# RP2350.net
KiCad netlist of a schematic drawn in Altium Designer
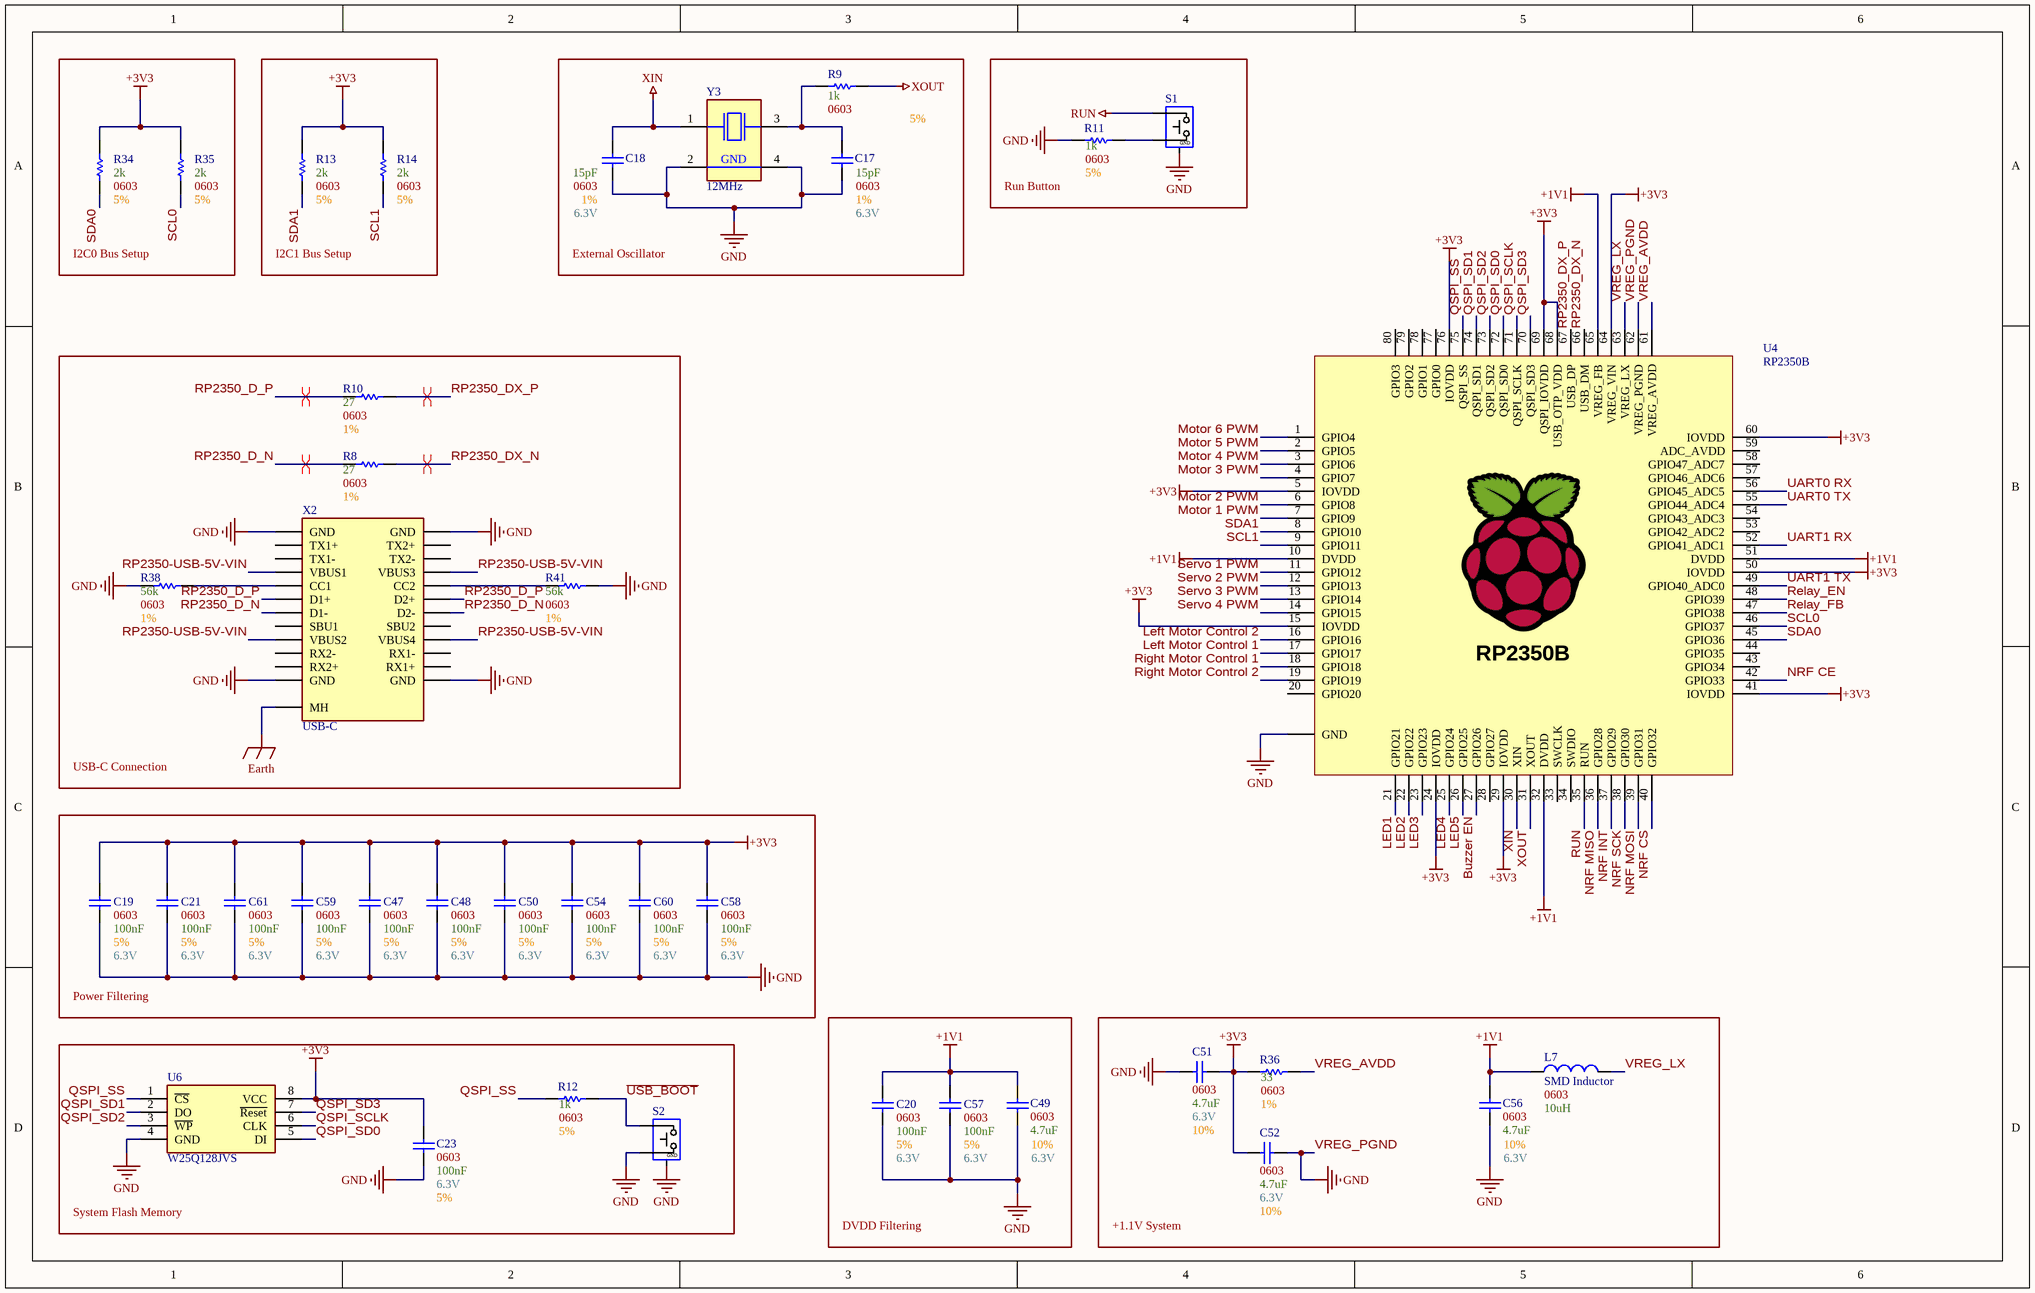
[diagram p0: RP2350.SchDoc]

(export (version "E")
  (design (tool "Eeschema 10.0.6"))
  (components
    (comp (ref "C17")
      (value "[Cap] SMD Nonpolarized")
      (footprint "[Cap] SMD 0603")
      (fields
        (field (name "SIZE PACKAGE") "0603")
        (field (name "CAPACITANCE") "15pF")
        (field (name "VOLTAGE") "6.3V")
        (field (name "TOLERANCE") "1%")
      )
      (libsource (lib "RADM Components") (part "[Cap] SMD Nonpolarized"))
    )
    (comp (ref "C18")
      (value "[Cap] SMD Nonpolarized")
      (footprint "[Cap] SMD 0603")
      (fields
        (field (name "SIZE PACKAGE") "0603")
        (field (name "CAPACITANCE") "15pF")
        (field (name "VOLTAGE") "6.3V")
        (field (name "TOLERANCE") "1%")
      )
      (libsource (lib "RADM Components") (part "[Cap] SMD Nonpolarized"))
    )
    (comp (ref "C19")
      (value "[Cap] SMD Nonpolarized")
      (footprint "[Cap] SMD 0603")
      (fields
        (field (name "SIZE PACKAGE") "0603")
        (field (name "CAPACITANCE") "100nF")
        (field (name "VOLTAGE") "6.3V")
        (field (name "TOLERANCE") "5%")
      )
      (libsource (lib "RADM Components") (part "[Cap] SMD Nonpolarized"))
    )
    (comp (ref "C20")
      (value "[Cap] SMD Nonpolarized")
      (footprint "[Cap] SMD 0603")
      (fields
        (field (name "SIZE PACKAGE") "0603")
        (field (name "CAPACITANCE") "100nF")
        (field (name "VOLTAGE") "6.3V")
        (field (name "TOLERANCE") "5%")
      )
      (libsource (lib "RADM Components") (part "[Cap] SMD Nonpolarized"))
    )
    (comp (ref "C21")
      (value "[Cap] SMD Nonpolarized")
      (footprint "[Cap] SMD 0603")
      (fields
        (field (name "SIZE PACKAGE") "0603")
        (field (name "CAPACITANCE") "100nF")
        (field (name "VOLTAGE") "6.3V")
        (field (name "TOLERANCE") "5%")
      )
      (libsource (lib "RADM Components") (part "[Cap] SMD Nonpolarized"))
    )
    (comp (ref "C23")
      (value "[Cap] SMD Nonpolarized")
      (footprint "[Cap] SMD 0603")
      (fields
        (field (name "SIZE PACKAGE") "0603")
        (field (name "CAPACITANCE") "100nF")
        (field (name "VOLTAGE") "6.3V")
        (field (name "TOLERANCE") "5%")
      )
      (libsource (lib "RADM Components") (part "[Cap] SMD Nonpolarized"))
    )
    (comp (ref "C47")
      (value "[Cap] SMD Nonpolarized")
      (footprint "[Cap] SMD 0603")
      (fields
        (field (name "SIZE PACKAGE") "0603")
        (field (name "CAPACITANCE") "100nF")
        (field (name "VOLTAGE") "6.3V")
        (field (name "TOLERANCE") "5%")
      )
      (libsource (lib "RADM Components") (part "[Cap] SMD Nonpolarized"))
    )
    (comp (ref "C48")
      (value "[Cap] SMD Nonpolarized")
      (footprint "[Cap] SMD 0603")
      (fields
        (field (name "SIZE PACKAGE") "0603")
        (field (name "CAPACITANCE") "100nF")
        (field (name "VOLTAGE") "6.3V")
        (field (name "TOLERANCE") "5%")
      )
      (libsource (lib "RADM Components") (part "[Cap] SMD Nonpolarized"))
    )
    (comp (ref "C49")
      (value "[Cap] SMD Nonpolarized")
      (footprint "[Cap] SMD 0603")
      (fields
        (field (name "SIZE PACKAGE") "0603")
        (field (name "CAPACITANCE") "4.7uF")
        (field (name "VOLTAGE") "6.3V")
        (field (name "TOLERANCE") "10%")
      )
      (libsource (lib "RADM Components") (part "[Cap] SMD Nonpolarized"))
    )
    (comp (ref "C50")
      (value "[Cap] SMD Nonpolarized")
      (footprint "[Cap] SMD 0603")
      (fields
        (field (name "SIZE PACKAGE") "0603")
        (field (name "CAPACITANCE") "100nF")
        (field (name "VOLTAGE") "6.3V")
        (field (name "TOLERANCE") "5%")
      )
      (libsource (lib "RADM Components") (part "[Cap] SMD Nonpolarized"))
    )
    (comp (ref "C51")
      (value "[Cap] SMD Nonpolarized")
      (footprint "[Cap] SMD 0603")
      (fields
        (field (name "SIZE PACKAGE") "0603")
        (field (name "CAPACITANCE") "4.7uF")
        (field (name "VOLTAGE") "6.3V")
        (field (name "TOLERANCE") "10%")
      )
      (libsource (lib "RADM Components") (part "[Cap] SMD Nonpolarized"))
    )
    (comp (ref "C52")
      (value "[Cap] SMD Nonpolarized")
      (footprint "[Cap] SMD 0603")
      (fields
        (field (name "SIZE PACKAGE") "0603")
        (field (name "CAPACITANCE") "4.7uF")
        (field (name "VOLTAGE") "6.3V")
        (field (name "TOLERANCE") "10%")
      )
      (libsource (lib "RADM Components") (part "[Cap] SMD Nonpolarized"))
    )
    (comp (ref "C54")
      (value "[Cap] SMD Nonpolarized")
      (footprint "[Cap] SMD 0603")
      (fields
        (field (name "SIZE PACKAGE") "0603")
        (field (name "CAPACITANCE") "100nF")
        (field (name "VOLTAGE") "6.3V")
        (field (name "TOLERANCE") "5%")
      )
      (libsource (lib "RADM Components") (part "[Cap] SMD Nonpolarized"))
    )
    (comp (ref "C56")
      (value "[Cap] SMD Nonpolarized")
      (footprint "[Cap] SMD 0603")
      (fields
        (field (name "SIZE PACKAGE") "0603")
        (field (name "CAPACITANCE") "4.7uF")
        (field (name "VOLTAGE") "6.3V")
        (field (name "TOLERANCE") "10%")
      )
      (libsource (lib "RADM Components") (part "[Cap] SMD Nonpolarized"))
    )
    (comp (ref "C57")
      (value "[Cap] SMD Nonpolarized")
      (footprint "[Cap] SMD 0603")
      (fields
        (field (name "SIZE PACKAGE") "0603")
        (field (name "CAPACITANCE") "100nF")
        (field (name "VOLTAGE") "6.3V")
        (field (name "TOLERANCE") "5%")
      )
      (libsource (lib "RADM Components") (part "[Cap] SMD Nonpolarized"))
    )
    (comp (ref "C58")
      (value "[Cap] SMD Nonpolarized")
      (footprint "[Cap] SMD 0603")
      (fields
        (field (name "SIZE PACKAGE") "0603")
        (field (name "CAPACITANCE") "100nF")
        (field (name "VOLTAGE") "6.3V")
        (field (name "TOLERANCE") "5%")
      )
      (libsource (lib "RADM Components") (part "[Cap] SMD Nonpolarized"))
    )
    (comp (ref "C59")
      (value "[Cap] SMD Nonpolarized")
      (footprint "[Cap] SMD 0603")
      (fields
        (field (name "SIZE PACKAGE") "0603")
        (field (name "CAPACITANCE") "100nF")
        (field (name "VOLTAGE") "6.3V")
        (field (name "TOLERANCE") "5%")
      )
      (libsource (lib "RADM Components") (part "[Cap] SMD Nonpolarized"))
    )
    (comp (ref "C60")
      (value "[Cap] SMD Nonpolarized")
      (footprint "[Cap] SMD 0603")
      (fields
        (field (name "SIZE PACKAGE") "0603")
        (field (name "CAPACITANCE") "100nF")
        (field (name "VOLTAGE") "6.3V")
        (field (name "TOLERANCE") "5%")
      )
      (libsource (lib "RADM Components") (part "[Cap] SMD Nonpolarized"))
    )
    (comp (ref "C61")
      (value "[Cap] SMD Nonpolarized")
      (footprint "[Cap] SMD 0603")
      (fields
        (field (name "SIZE PACKAGE") "0603")
        (field (name "CAPACITANCE") "100nF")
        (field (name "VOLTAGE") "6.3V")
        (field (name "TOLERANCE") "5%")
      )
      (libsource (lib "RADM Components") (part "[Cap] SMD Nonpolarized"))
    )
    (comp (ref "L7")
      (value "SMD Inductor")
      (footprint "[Inductor] SMD 0603")
      (fields (field (name "SIZE PACKAGE") "0603") (field (name "INDUCTANCE") "10uH"))
      (libsource (lib "RADM Components") (part "[Inductor] SMD Inductor"))
    )
    (comp (ref "R8")
      (value "[Res] SMD Resistor")
      (footprint "[Res] SMD 0603")
      (description "Generic")
      (fields
        (field (name "TOLERANCE") "1%")
        (field (name "RESISTANCE") "27")
        (field (name "SIZE PACKAGE") "0603")
      )
      (libsource (lib "RADM Components") (part "[Res] SMD Resistor"))
    )
    (comp (ref "R9")
      (value "[Res] SMD Resistor")
      (footprint "[Res] SMD 0603")
      (description "Generic")
      (fields
        (field (name "RESISTANCE") "1k")
        (field (name "SIZE PACKAGE") "0603")
        (field (name "TOLERANCE") "5%")
      )
      (libsource (lib "RADM Components") (part "[Res] SMD Resistor"))
    )
    (comp (ref "R10")
      (value "[Res] SMD Resistor")
      (footprint "[Res] SMD 0603")
      (description "Generic")
      (fields
        (field (name "TOLERANCE") "1%")
        (field (name "RESISTANCE") "27")
        (field (name "SIZE PACKAGE") "0603")
      )
      (libsource (lib "RADM Components") (part "[Res] SMD Resistor"))
    )
    (comp (ref "R11")
      (value "[Res] SMD Resistor")
      (footprint "[Res] SMD 0603")
      (description "Generic")
      (fields
        (field (name "RESISTANCE") "1k")
        (field (name "SIZE PACKAGE") "0603")
        (field (name "TOLERANCE") "5%")
      )
      (libsource (lib "RADM Components") (part "[Res] SMD Resistor"))
    )
    (comp (ref "R12")
      (value "[Res] SMD Resistor")
      (footprint "[Res] SMD 0603")
      (description "Generic")
      (fields
        (field (name "RESISTANCE") "1k")
        (field (name "SIZE PACKAGE") "0603")
        (field (name "TOLERANCE") "5%")
      )
      (libsource (lib "RADM Components") (part "[Res] SMD Resistor"))
    )
    (comp (ref "R13")
      (value "[Res] SMD Resistor")
      (footprint "[Res] SMD 0603")
      (description "Generic")
      (fields
        (field (name "RESISTANCE") "2k")
        (field (name "SIZE PACKAGE") "0603")
        (field (name "TOLERANCE") "5%")
      )
      (libsource (lib "RADM Components") (part "[Res] SMD Resistor"))
    )
    (comp (ref "R14")
      (value "[Res] SMD Resistor")
      (footprint "[Res] SMD 0603")
      (description "Generic")
      (fields
        (field (name "RESISTANCE") "2k")
        (field (name "SIZE PACKAGE") "0603")
        (field (name "TOLERANCE") "5%")
      )
      (libsource (lib "RADM Components") (part "[Res] SMD Resistor"))
    )
    (comp (ref "R34")
      (value "[Res] SMD Resistor")
      (footprint "[Res] SMD 0603")
      (description "Generic")
      (fields
        (field (name "RESISTANCE") "2k")
        (field (name "SIZE PACKAGE") "0603")
        (field (name "TOLERANCE") "5%")
      )
      (libsource (lib "RADM Components") (part "[Res] SMD Resistor"))
    )
    (comp (ref "R35")
      (value "[Res] SMD Resistor")
      (footprint "[Res] SMD 0603")
      (description "Generic")
      (fields
        (field (name "RESISTANCE") "2k")
        (field (name "SIZE PACKAGE") "0603")
        (field (name "TOLERANCE") "5%")
      )
      (libsource (lib "RADM Components") (part "[Res] SMD Resistor"))
    )
    (comp (ref "R36")
      (value "[Res] SMD Resistor")
      (footprint "[Res] SMD 0603")
      (description "Generic")
      (fields
        (field (name "RESISTANCE") "33")
        (field (name "SIZE PACKAGE") "0603")
        (field (name "TOLERANCE") "1%")
      )
      (libsource (lib "RADM Components") (part "[Res] SMD Resistor"))
    )
    (comp (ref "R38")
      (value "[Res] SMD Resistor")
      (footprint "[Res] SMD 0603")
      (description "Generic")
      (fields
        (field (name "TOLERANCE") "1%")
        (field (name "RESISTANCE") "56k")
        (field (name "SIZE PACKAGE") "0603")
      )
      (libsource (lib "RADM Components") (part "[Res] SMD Resistor"))
    )
    (comp (ref "R41")
      (value "[Res] SMD Resistor")
      (footprint "[Res] SMD 0603")
      (description "Generic")
      (fields
        (field (name "TOLERANCE") "1%")
        (field (name "RESISTANCE") "56k")
        (field (name "SIZE PACKAGE") "0603")
      )
      (libsource (lib "RADM Components") (part "[Res] SMD Resistor"))
    )
    (comp (ref "S1")
      (value "[Switch] Pushbutton SMD")
      (footprint "[Switch] Pushbutton SMD 2")
      (libsource (lib "RADM Components") (part "[Switch] Pushbutton SMD"))
    )
    (comp (ref "S2")
      (value "[Switch] Pushbutton SMD")
      (footprint "[Switch] Pushbutton SMD 2")
      (libsource (lib "RADM Components") (part "[Switch] Pushbutton SMD"))
    )
    (comp (ref "U4")
      (value "RP2350B")
      (footprint "[MCU] RP2350B")
      (description "QFN-80 Package")
      (libsource (lib "RADM Components") (part "[MCU] RP2350B"))
    )
    (comp (ref "U6")
      (value "W25Q128JVS")
      (footprint "[Mem] 16Mb Flash Memory")
      (description "W25Q128JVSIQ TR")
      (libsource (lib "RADM Components") (part "[Mem] 16Mb Flash Memory"))
    )
    (comp (ref "X2")
      (value "USB-C")
      (footprint "[Port] USB-C")
      (libsource (lib "RADM Connectors") (part "[Port] USB Type-C"))
    )
    (comp (ref "Y3")
      (value "12MHz")
      (footprint "[XTAL] SMD 12MHz")
      (description "815-ABM8-272-T3")
      (libsource (lib "RADM Components") (part "[XTAL] SMD 12MHz"))
    )
  )
  (nets
    (net (code "1") (name "+1V1") (class "Default")
      (node (ref "C20") (pin "2") (pinfunction "2_2") (pintype "passive"))
      (node (ref "C49") (pin "2") (pinfunction "2_2") (pintype "passive"))
      (node (ref "C56") (pin "2") (pinfunction "2_2") (pintype "passive"))
      (node (ref "C57") (pin "2") (pinfunction "2_2") (pintype "passive"))
      (node (ref "L7") (pin "1") (pinfunction "1_1") (pintype "passive"))
      (node (ref "U4") (pin "10") (pinfunction "DVDD_10") (pintype "passive"))
      (node (ref "U4") (pin "32") (pinfunction "DVDD_32") (pintype "passive"))
      (node (ref "U4") (pin "51") (pinfunction "DVDD_51") (pintype "passive"))
      (node (ref "U4") (pin "65") (pinfunction "VREG_FB_65") (pintype "passive"))
    )
    (net (code "2") (name "+3V3") (class "Default")
      (node (ref "C19") (pin "2") (pinfunction "2_2") (pintype "passive"))
      (node (ref "C21") (pin "2") (pinfunction "2_2") (pintype "passive"))
      (node (ref "C23") (pin "1") (pinfunction "1_1") (pintype "passive"))
      (node (ref "C47") (pin "2") (pinfunction "2_2") (pintype "passive"))
      (node (ref "C48") (pin "2") (pinfunction "2_2") (pintype "passive"))
      (node (ref "C50") (pin "2") (pinfunction "2_2") (pintype "passive"))
      (node (ref "C51") (pin "1") (pinfunction "1_1") (pintype "passive"))
      (node (ref "C52") (pin "2") (pinfunction "2_2") (pintype "passive"))
      (node (ref "C54") (pin "2") (pinfunction "2_2") (pintype "passive"))
      (node (ref "C58") (pin "2") (pinfunction "2_2") (pintype "passive"))
      (node (ref "C59") (pin "2") (pinfunction "2_2") (pintype "passive"))
      (node (ref "C60") (pin "2") (pinfunction "2_2") (pintype "passive"))
      (node (ref "C61") (pin "2") (pinfunction "2_2") (pintype "passive"))
      (node (ref "R13") (pin "2") (pinfunction "2_2") (pintype "passive"))
      (node (ref "R14") (pin "2") (pinfunction "2_2") (pintype "passive"))
      (node (ref "R34") (pin "2") (pinfunction "2_2") (pintype "passive"))
      (node (ref "R35") (pin "2") (pinfunction "2_2") (pintype "passive"))
      (node (ref "R36") (pin "2") (pinfunction "2_2") (pintype "passive"))
      (node (ref "U4") (pin "15") (pinfunction "IOVDD_15") (pintype "passive"))
      (node (ref "U4") (pin "24") (pinfunction "IOVDD_24") (pintype "passive"))
      (node (ref "U4") (pin "29") (pinfunction "IOVDD_29") (pintype "passive"))
      (node (ref "U4") (pin "41") (pinfunction "IOVDD_41") (pintype "passive"))
      (node (ref "U4") (pin "5") (pinfunction "IOVDD_5") (pintype "passive"))
      (node (ref "U4") (pin "50") (pinfunction "IOVDD_50") (pintype "passive"))
      (node (ref "U4") (pin "60") (pinfunction "IOVDD_60") (pintype "passive"))
      (node (ref "U4") (pin "64") (pinfunction "VREG_VIN_64") (pintype "passive"))
      (node (ref "U4") (pin "68") (pinfunction "USB_OTP_VDD_68") (pintype "passive"))
      (node (ref "U4") (pin "69") (pinfunction "QSPI_IOVDD_69") (pintype "passive"))
      (node (ref "U4") (pin "76") (pinfunction "IOVDD_76") (pintype "passive"))
      (node (ref "U6") (pin "8") (pinfunction "VCC_8") (pintype "passive"))
    )
    (net (code "3") (name "/Buzzer EN") (class "Default")
      (node (ref "U4") (pin "27") (pinfunction "GPIO26_27") (pintype "passive"))
    )
    (net (code "4") (name "/LED1") (class "Default")
      (node (ref "U4") (pin "21") (pinfunction "GPIO21_21") (pintype "passive"))
    )
    (net (code "5") (name "/LED2") (class "Default")
      (node (ref "U4") (pin "22") (pinfunction "GPIO22_22") (pintype "passive"))
    )
    (net (code "6") (name "/LED3") (class "Default")
      (node (ref "U4") (pin "23") (pinfunction "GPIO23_23") (pintype "passive"))
    )
    (net (code "7") (name "/LED4") (class "Default")
      (node (ref "U4") (pin "25") (pinfunction "GPIO24_25") (pintype "passive"))
    )
    (net (code "8") (name "/LED5") (class "Default")
      (node (ref "U4") (pin "26") (pinfunction "GPIO25_26") (pintype "passive"))
    )
    (net (code "9") (name "/Left Motor Control 1") (class "Default")
      (node (ref "U4") (pin "17") (pinfunction "GPIO17_17") (pintype "passive"))
    )
    (net (code "10") (name "/Left Motor Control 2") (class "Default")
      (node (ref "U4") (pin "16") (pinfunction "GPIO16_16") (pintype "passive"))
    )
    (net (code "11") (name "/Motor 1 PWM") (class "Default")
      (node (ref "U4") (pin "7") (pinfunction "GPIO9_7") (pintype "passive"))
    )
    (net (code "12") (name "/Motor 2 PWM") (class "Default")
      (node (ref "U4") (pin "6") (pinfunction "GPIO8_6") (pintype "passive"))
    )
    (net (code "13") (name "/Motor 3 PWM") (class "Default")
      (node (ref "U4") (pin "4") (pinfunction "GPIO7_4") (pintype "passive"))
    )
    (net (code "14") (name "/Motor 4 PWM") (class "Default")
      (node (ref "U4") (pin "3") (pinfunction "GPIO6_3") (pintype "passive"))
    )
    (net (code "15") (name "/Motor 5 PWM") (class "Default")
      (node (ref "U4") (pin "2") (pinfunction "GPIO5_2") (pintype "passive"))
    )
    (net (code "16") (name "/Motor 6 PWM") (class "Default")
      (node (ref "U4") (pin "1") (pinfunction "GPIO4_1") (pintype "passive"))
    )
    (net (code "17") (name "/NRF CE") (class "Default")
      (node (ref "U4") (pin "42") (pinfunction "GPIO33_42") (pintype "passive"))
    )
    (net (code "18") (name "/NRF CS") (class "Default")
      (node (ref "U4") (pin "40") (pinfunction "GPIO32_40") (pintype "passive"))
    )
    (net (code "19") (name "/NRF INT") (class "Default")
      (node (ref "U4") (pin "37") (pinfunction "GPIO29_37") (pintype "passive"))
    )
    (net (code "20") (name "/NRF MISO") (class "Default")
      (node (ref "U4") (pin "36") (pinfunction "GPIO28_36") (pintype "passive"))
    )
    (net (code "21") (name "/NRF MOSI") (class "Default")
      (node (ref "U4") (pin "39") (pinfunction "GPIO31_39") (pintype "passive"))
    )
    (net (code "22") (name "/NRF SCK") (class "Default")
      (node (ref "U4") (pin "38") (pinfunction "GPIO30_38") (pintype "passive"))
    )
    (net (code "23") (name "/QSPI_SCLK") (class "Default")
      (node (ref "U4") (pin "71") (pinfunction "QSPI_SCLK_71") (pintype "passive"))
      (node (ref "U6") (pin "6") (pinfunction "CLK_6") (pintype "passive"))
    )
    (net (code "24") (name "/QSPI_SD0") (class "Default")
      (node (ref "U4") (pin "72") (pinfunction "QSPI_SD0_72") (pintype "passive"))
      (node (ref "U6") (pin "5") (pinfunction "DI_5") (pintype "passive"))
    )
    (net (code "25") (name "/QSPI_SD1") (class "Default")
      (node (ref "U4") (pin "74") (pinfunction "QSPI_SD1_74") (pintype "passive"))
      (node (ref "U6") (pin "2") (pinfunction "DO_2") (pintype "passive"))
    )
    (net (code "26") (name "/QSPI_SD2") (class "Default")
      (node (ref "U4") (pin "73") (pinfunction "QSPI_SD2_73") (pintype "passive"))
      (node (ref "U6") (pin "3") (pinfunction "~{WP}_3") (pintype "passive"))
    )
    (net (code "27") (name "/QSPI_SD3") (class "Default")
      (node (ref "U4") (pin "70") (pinfunction "QSPI_SD3_70") (pintype "passive"))
      (node (ref "U6") (pin "7") (pinfunction "~{Reset}_7") (pintype "passive"))
    )
    (net (code "28") (name "/QSPI_SS") (class "Default")
      (node (ref "R12") (pin "2") (pinfunction "2_2") (pintype "passive"))
      (node (ref "U4") (pin "75") (pinfunction "QSPI_SS_75") (pintype "passive"))
      (node (ref "U6") (pin "1") (pinfunction "~{CS}_1") (pintype "passive"))
    )
    (net (code "29") (name "/RP2350-USB-5V-VIN") (class "Default")
      (node (ref "X2") (pin "A4") (pinfunction "VBUS1_A4") (pintype "passive"))
      (node (ref "X2") (pin "A9") (pinfunction "VBUS2_A9") (pintype "passive"))
      (node (ref "X2") (pin "B4") (pinfunction "VBUS3_B4") (pintype "passive"))
      (node (ref "X2") (pin "B9") (pinfunction "VBUS4_B9") (pintype "passive"))
    )
    (net (code "30") (name "/RP2350_DX_N") (class "Default")
      (node (ref "R8") (pin "2") (pinfunction "2_2") (pintype "passive"))
      (node (ref "U4") (pin "66") (pinfunction "USB_DM_66") (pintype "passive"))
    )
    (net (code "31") (name "/RP2350_DX_P") (class "Default")
      (node (ref "R10") (pin "2") (pinfunction "2_2") (pintype "passive"))
      (node (ref "U4") (pin "67") (pinfunction "USB_DP_67") (pintype "passive"))
    )
    (net (code "32") (name "/RP2350_D_N") (class "Default")
      (node (ref "R8") (pin "1") (pinfunction "1_1") (pintype "passive"))
      (node (ref "X2") (pin "A7") (pinfunction "D1-_A7") (pintype "passive"))
      (node (ref "X2") (pin "B7") (pinfunction "D2-_B7") (pintype "passive"))
    )
    (net (code "33") (name "/RP2350_D_P") (class "Default")
      (node (ref "R10") (pin "1") (pinfunction "1_1") (pintype "passive"))
      (node (ref "X2") (pin "A6") (pinfunction "D1+_A6") (pintype "passive"))
      (node (ref "X2") (pin "B6") (pinfunction "D2+_B6") (pintype "passive"))
    )
    (net (code "34") (name "/Relay_EN") (class "Default")
      (node (ref "U4") (pin "48") (pinfunction "GPIO39_48") (pintype "passive"))
    )
    (net (code "35") (name "/Relay_FB") (class "Default")
      (node (ref "U4") (pin "47") (pinfunction "GPIO38_47") (pintype "passive"))
    )
    (net (code "36") (name "/Right Motor Control 1") (class "Default")
      (node (ref "U4") (pin "18") (pinfunction "GPIO18_18") (pintype "passive"))
    )
    (net (code "37") (name "/Right Motor Control 2") (class "Default")
      (node (ref "U4") (pin "19") (pinfunction "GPIO19_19") (pintype "passive"))
    )
    (net (code "38") (name "/SCL0") (class "Default")
      (node (ref "R35") (pin "1") (pinfunction "1_1") (pintype "passive"))
      (node (ref "U4") (pin "46") (pinfunction "GPIO37_46") (pintype "passive"))
    )
    (net (code "39") (name "/SCL1") (class "Default")
      (node (ref "R14") (pin "1") (pinfunction "1_1") (pintype "passive"))
      (node (ref "U4") (pin "9") (pinfunction "GPIO11_9") (pintype "passive"))
    )
    (net (code "40") (name "/SDA0") (class "Default")
      (node (ref "R34") (pin "1") (pinfunction "1_1") (pintype "passive"))
      (node (ref "U4") (pin "45") (pinfunction "GPIO36_45") (pintype "passive"))
    )
    (net (code "41") (name "/SDA1") (class "Default")
      (node (ref "R13") (pin "1") (pinfunction "1_1") (pintype "passive"))
      (node (ref "U4") (pin "8") (pinfunction "GPIO10_8") (pintype "passive"))
    )
    (net (code "42") (name "/Servo 1 PWM") (class "Default")
      (node (ref "U4") (pin "11") (pinfunction "GPIO12_11") (pintype "passive"))
    )
    (net (code "43") (name "/Servo 2 PWM") (class "Default")
      (node (ref "U4") (pin "12") (pinfunction "GPIO13_12") (pintype "passive"))
    )
    (net (code "44") (name "/Servo 3 PWM") (class "Default")
      (node (ref "U4") (pin "13") (pinfunction "GPIO14_13") (pintype "passive"))
    )
    (net (code "45") (name "/Servo 4 PWM") (class "Default")
      (node (ref "U4") (pin "14") (pinfunction "GPIO15_14") (pintype "passive"))
    )
    (net (code "46") (name "/UART0 RX") (class "Default")
      (node (ref "U4") (pin "56") (pinfunction "GPIO45_ADC5_56") (pintype "passive"))
    )
    (net (code "47") (name "/UART0 TX") (class "Default")
      (node (ref "U4") (pin "55") (pinfunction "GPIO44_ADC4_55") (pintype "passive"))
    )
    (net (code "48") (name "/UART1 RX") (class "Default")
      (node (ref "U4") (pin "52") (pinfunction "GPIO41_ADC1_52") (pintype "passive"))
    )
    (net (code "49") (name "/UART1 TX") (class "Default")
      (node (ref "U4") (pin "49") (pinfunction "GPIO40_ADC0_49") (pintype "passive"))
    )
    (net (code "50") (name "/VREG_AVDD") (class "Default")
      (node (ref "R36") (pin "1") (pinfunction "1_1") (pintype "passive"))
      (node (ref "U4") (pin "61") (pinfunction "VREG_AVDD_61") (pintype "passive"))
    )
    (net (code "51") (name "/VREG_LX") (class "Default")
      (node (ref "L7") (pin "2") (pinfunction "2_2") (pintype "passive"))
      (node (ref "U4") (pin "63") (pinfunction "VREG_LX_63") (pintype "passive"))
    )
    (net (code "52") (name "/~{USB_BOOT}") (class "Default")
      (node (ref "R12") (pin "1") (pinfunction "1_1") (pintype "passive"))
      (node (ref "S2") (pin "1") (pintype "power_in"))
    )
    (net (code "53") (name "Earth") (class "Default")
      (node (ref "X2") (pin "MH") (pinfunction "MH_MH") (pintype "passive"))
    )
    (net (code "54") (name "GND") (class "Default")
      (node (ref "C17") (pin "1") (pinfunction "1_1") (pintype "passive"))
      (node (ref "C18") (pin "1") (pinfunction "1_1") (pintype "passive"))
      (node (ref "C19") (pin "1") (pinfunction "1_1") (pintype "passive"))
      (node (ref "C20") (pin "1") (pinfunction "1_1") (pintype "passive"))
      (node (ref "C21") (pin "1") (pinfunction "1_1") (pintype "passive"))
      (node (ref "C23") (pin "2") (pinfunction "2_2") (pintype "passive"))
      (node (ref "C47") (pin "1") (pinfunction "1_1") (pintype "passive"))
      (node (ref "C48") (pin "1") (pinfunction "1_1") (pintype "passive"))
      (node (ref "C49") (pin "1") (pinfunction "1_1") (pintype "passive"))
      (node (ref "C50") (pin "1") (pinfunction "1_1") (pintype "passive"))
      (node (ref "C51") (pin "2") (pinfunction "2_2") (pintype "passive"))
      (node (ref "C52") (pin "1") (pinfunction "1_1") (pintype "passive"))
      (node (ref "C54") (pin "1") (pinfunction "1_1") (pintype "passive"))
      (node (ref "C56") (pin "1") (pinfunction "1_1") (pintype "passive"))
      (node (ref "C57") (pin "1") (pinfunction "1_1") (pintype "passive"))
      (node (ref "C58") (pin "1") (pinfunction "1_1") (pintype "passive"))
      (node (ref "C59") (pin "1") (pinfunction "1_1") (pintype "passive"))
      (node (ref "C60") (pin "1") (pinfunction "1_1") (pintype "passive"))
      (node (ref "C61") (pin "1") (pinfunction "1_1") (pintype "passive"))
      (node (ref "R11") (pin "2") (pinfunction "2_2") (pintype "passive"))
      (node (ref "R38") (pin "1") (pinfunction "1_1") (pintype "passive"))
      (node (ref "R41") (pin "2") (pinfunction "2_2") (pintype "passive"))
      (node (ref "S1") (pin "GND") (pinfunction "GND_GND") (pintype "power_in"))
      (node (ref "S2") (pin "2") (pintype "power_in"))
      (node (ref "S2") (pin "GND") (pinfunction "GND_GND") (pintype "power_in"))
      (node (ref "U4") (pin "62") (pinfunction "VREG_PGND_62") (pintype "passive"))
      (node (ref "U4") (pin "Pad") (pinfunction "GND_Pad") (pintype "passive"))
      (node (ref "U6") (pin "4") (pinfunction "GND_4") (pintype "passive"))
      (node (ref "X2") (pin "A1") (pinfunction "GND_A1") (pintype "passive"))
      (node (ref "X2") (pin "A12") (pinfunction "GND_A12") (pintype "passive"))
      (node (ref "X2") (pin "B1") (pinfunction "GND_B1") (pintype "passive"))
      (node (ref "X2") (pin "B12") (pinfunction "GND_B12") (pintype "passive"))
      (node (ref "Y3") (pin "2") (pinfunction "GND_2") (pintype "power_in"))
      (node (ref "Y3") (pin "4") (pinfunction "GND_4") (pintype "power_in"))
    )
    (net (code "55") (name "Net-(R11-Pad1)") (class "Default")
      (node (ref "R11") (pin "1") (pinfunction "1_1") (pintype "passive"))
      (node (ref "S1") (pin "2") (pintype "power_in"))
    )
    (net (code "56") (name "Net-(X2-CC1)") (class "Default")
      (node (ref "R38") (pin "2") (pinfunction "2_2") (pintype "passive"))
      (node (ref "X2") (pin "A5") (pinfunction "CC1_A5") (pintype "passive"))
    )
    (net (code "57") (name "Net-(X2-CC2)") (class "Default")
      (node (ref "R41") (pin "1") (pinfunction "1_1") (pintype "passive"))
      (node (ref "X2") (pin "B5") (pinfunction "CC2_B5") (pintype "passive"))
    )
    (net (code "58") (name "Net-(Y3-XTAL2)") (class "Default")
      (node (ref "C17") (pin "2") (pinfunction "2_2") (pintype "passive"))
      (node (ref "R9") (pin "2") (pinfunction "2_2") (pintype "passive"))
      (node (ref "Y3") (pin "3") (pinfunction "XTAL2_3") (pintype "power_in"))
    )
    (net (code "59") (name "RUN") (class "Default")
      (node (ref "S1") (pin "1") (pintype "power_in"))
      (node (ref "U4") (pin "35") (pinfunction "RUN_35") (pintype "passive"))
    )
    (net (code "60") (name "XIN") (class "Default")
      (node (ref "C18") (pin "2") (pinfunction "2_2") (pintype "passive"))
      (node (ref "U4") (pin "30") (pinfunction "XIN_30") (pintype "passive"))
      (node (ref "Y3") (pin "1") (pinfunction "XTAL1_1") (pintype "power_in"))
    )
    (net (code "61") (name "XOUT") (class "Default")
      (node (ref "R9") (pin "1") (pinfunction "1_1") (pintype "passive"))
      (node (ref "U4") (pin "31") (pinfunction "XOUT_31") (pintype "passive"))
    )
    (net (code "62") (name "unconnected-(U4-ADC_AVDD-Pad59)") (class "Default")
      (node (ref "U4") (pin "59") (pinfunction "ADC_AVDD_59") (pintype "passive"))
    )
    (net (code "63") (name "unconnected-(U4-GPIO0-Pad77)") (class "Default")
      (node (ref "U4") (pin "77") (pinfunction "GPIO0_77") (pintype "passive"))
    )
    (net (code "64") (name "unconnected-(U4-GPIO1-Pad78)") (class "Default")
      (node (ref "U4") (pin "78") (pinfunction "GPIO1_78") (pintype "passive"))
    )
    (net (code "65") (name "unconnected-(U4-GPIO2-Pad79)") (class "Default")
      (node (ref "U4") (pin "79") (pinfunction "GPIO2_79") (pintype "passive"))
    )
    (net (code "66") (name "unconnected-(U4-GPIO3-Pad80)") (class "Default")
      (node (ref "U4") (pin "80") (pinfunction "GPIO3_80") (pintype "passive"))
    )
    (net (code "67") (name "unconnected-(U4-GPIO20-Pad20)") (class "Default")
      (node (ref "U4") (pin "20") (pinfunction "GPIO20_20") (pintype "passive"))
    )
    (net (code "68") (name "unconnected-(U4-GPIO27-Pad28)") (class "Default")
      (node (ref "U4") (pin "28") (pinfunction "GPIO27_28") (pintype "passive"))
    )
    (net (code "69") (name "unconnected-(U4-GPIO34-Pad43)") (class "Default")
      (node (ref "U4") (pin "43") (pinfunction "GPIO34_43") (pintype "passive"))
    )
    (net (code "70") (name "unconnected-(U4-GPIO35-Pad44)") (class "Default")
      (node (ref "U4") (pin "44") (pinfunction "GPIO35_44") (pintype "passive"))
    )
    (net (code "71") (name "unconnected-(U4-GPIO42_ADC2-Pad53)") (class "Default")
      (node (ref "U4") (pin "53") (pinfunction "GPIO42_ADC2_53") (pintype "passive"))
    )
    (net (code "72") (name "unconnected-(U4-GPIO43_ADC3-Pad54)") (class "Default")
      (node (ref "U4") (pin "54") (pinfunction "GPIO43_ADC3_54") (pintype "passive"))
    )
    (net (code "73") (name "unconnected-(U4-GPIO46_ADC6-Pad57)") (class "Default")
      (node (ref "U4") (pin "57") (pinfunction "GPIO46_ADC6_57") (pintype "passive"))
    )
    (net (code "74") (name "unconnected-(U4-GPIO47_ADC7-Pad58)") (class "Default")
      (node (ref "U4") (pin "58") (pinfunction "GPIO47_ADC7_58") (pintype "passive"))
    )
    (net (code "75") (name "unconnected-(U4-SWCLK-Pad33)") (class "Default")
      (node (ref "U4") (pin "33") (pinfunction "SWCLK_33") (pintype "passive"))
    )
    (net (code "76") (name "unconnected-(U4-SWDIO-Pad34)") (class "Default")
      (node (ref "U4") (pin "34") (pinfunction "SWDIO_34") (pintype "passive"))
    )
    (net (code "77") (name "unconnected-(X2-RX1+-PadB11)") (class "Default")
      (node (ref "X2") (pin "B11") (pinfunction "RX1+_B11") (pintype "passive"))
    )
    (net (code "78") (name "unconnected-(X2-RX1--PadB10)") (class "Default")
      (node (ref "X2") (pin "B10") (pinfunction "RX1-_B10") (pintype "passive"))
    )
    (net (code "79") (name "unconnected-(X2-RX2+-PadA11)") (class "Default")
      (node (ref "X2") (pin "A11") (pinfunction "RX2+_A11") (pintype "passive"))
    )
    (net (code "80") (name "unconnected-(X2-RX2--PadA10)") (class "Default")
      (node (ref "X2") (pin "A10") (pinfunction "RX2-_A10") (pintype "passive"))
    )
    (net (code "81") (name "unconnected-(X2-SBU1-PadA8)") (class "Default")
      (node (ref "X2") (pin "A8") (pinfunction "SBU1_A8") (pintype "passive"))
    )
    (net (code "82") (name "unconnected-(X2-SBU2-PadB8)") (class "Default")
      (node (ref "X2") (pin "B8") (pinfunction "SBU2_B8") (pintype "passive"))
    )
    (net (code "83") (name "unconnected-(X2-TX1+-PadA2)") (class "Default")
      (node (ref "X2") (pin "A2") (pinfunction "TX1+_A2") (pintype "passive"))
    )
    (net (code "84") (name "unconnected-(X2-TX1--PadA3)") (class "Default")
      (node (ref "X2") (pin "A3") (pinfunction "TX1-_A3") (pintype "passive"))
    )
    (net (code "85") (name "unconnected-(X2-TX2+-PadB2)") (class "Default")
      (node (ref "X2") (pin "B2") (pinfunction "TX2+_B2") (pintype "passive"))
    )
    (net (code "86") (name "unconnected-(X2-TX2--PadB3)") (class "Default")
      (node (ref "X2") (pin "B3") (pinfunction "TX2-_B3") (pintype "passive"))
    )
  )
)
